# xxxxxx_001_sh1_RTC.net
KiCad netlist of a schematic drawn in Altium Designer
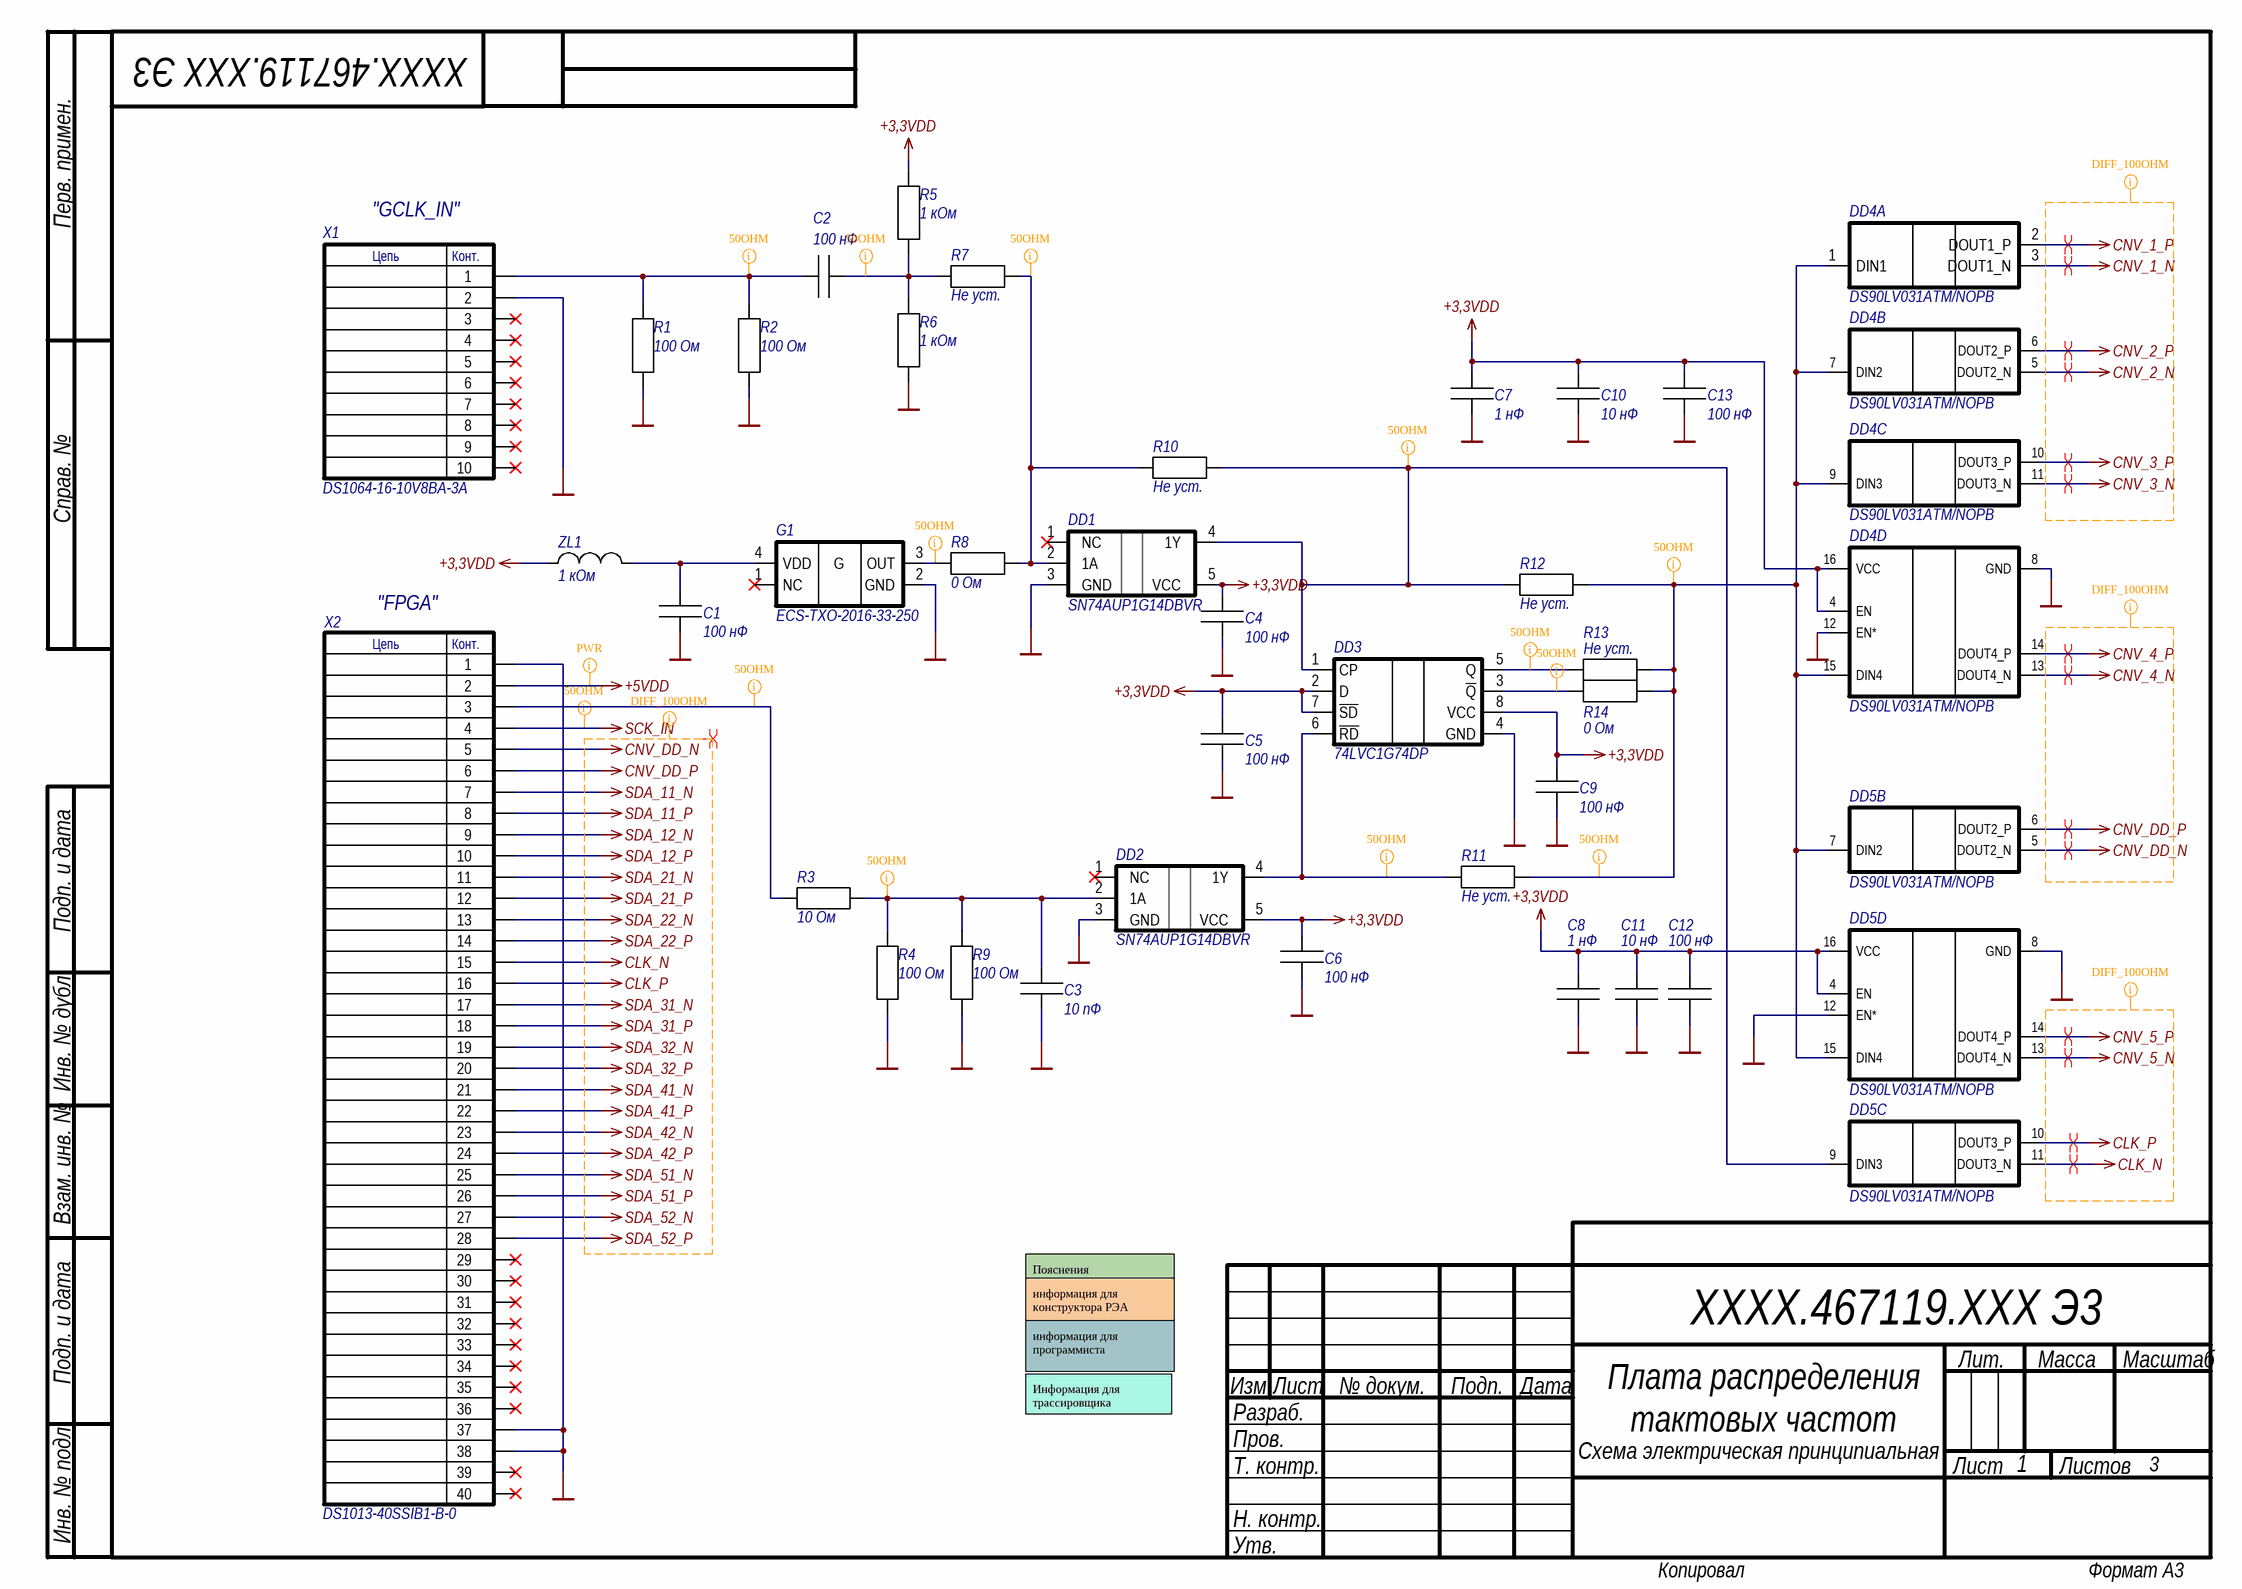
[diagram p0: xxxxxx.001_sh1_RTC.SchDoc]

(export (version "E")
  (design (tool "Eeschema 10.0.6"))
  (components
    (comp (ref "C1")
      (value "100 нФ")
      (footprint "CAPC160X080X080N")
      (description "Chip Monolithic Ceramic Capacitor")
      (fields (field (name "MANUFACTURER") "Murata") (field (name "VOLTAGE") "25 В"))
      (libsource (lib "xxxxxx001_RTC") (part "CAP_NP"))
    )
    (comp (ref "C2")
      (value "100 нФ")
      (footprint "CAPC160X080X080N")
      (description "Chip Monolithic Ceramic Capacitor")
      (fields (field (name "MANUFACTURER") "Murata") (field (name "VOLTAGE") "25 В"))
      (libsource (lib "xxxxxx001_RTC") (part "CAP_NP"))
    )
    (comp (ref "C3")
      (value "10 пФ")
      (footprint "CAPC160X080X080N")
      (description "Multilayer Ceramic Chip Capacitor")
      (fields (field (name "MANUFACTURER") "Yageo") (field (name "VOLTAGE") "50 В"))
      (libsource (lib "xxxxxx001_RTC") (part "CAP_NP"))
    )
    (comp (ref "C4")
      (value "100 нФ")
      (footprint "CAPC160X080X080N")
      (description "Chip Monolithic Ceramic Capacitor")
      (fields (field (name "MANUFACTURER") "Murata") (field (name "VOLTAGE") "25 В"))
      (libsource (lib "xxxxxx001_RTC") (part "CAP_NP"))
    )
    (comp (ref "C5")
      (value "100 нФ")
      (footprint "CAPC160X080X080N")
      (description "Chip Monolithic Ceramic Capacitor")
      (fields (field (name "MANUFACTURER") "Murata") (field (name "VOLTAGE") "25 В"))
      (libsource (lib "xxxxxx001_RTC") (part "CAP_NP"))
    )
    (comp (ref "C6")
      (value "100 нФ")
      (footprint "CAPC160X080X080N")
      (description "Chip Monolithic Ceramic Capacitor")
      (fields (field (name "MANUFACTURER") "Murata") (field (name "VOLTAGE") "25 В"))
      (libsource (lib "xxxxxx001_RTC") (part "CAP_NP"))
    )
    (comp (ref "C7")
      (value "1 нФ")
      (footprint "CAPC160X080X080N")
      (description "Chip Monolithic Ceramic Capacitor")
      (fields (field (name "MANUFACTURER") "Murata") (field (name "VOLTAGE") "50 В"))
      (libsource (lib "xxxxxx001_RTC") (part "CAP_NP"))
    )
    (comp (ref "C8")
      (value "1 нФ")
      (footprint "CAPC160X080X080N")
      (description "Chip Monolithic Ceramic Capacitor")
      (fields (field (name "MANUFACTURER") "Murata") (field (name "VOLTAGE") "50 В"))
      (libsource (lib "xxxxxx001_RTC") (part "CAP_NP"))
    )
    (comp (ref "C9")
      (value "100 нФ")
      (footprint "CAPC160X080X080N")
      (description "Chip Monolithic Ceramic Capacitor")
      (fields (field (name "MANUFACTURER") "Murata") (field (name "VOLTAGE") "25 В"))
      (libsource (lib "xxxxxx001_RTC") (part "CAP_NP"))
    )
    (comp (ref "C10")
      (value "10 нФ")
      (footprint "CAPC160X080X080N")
      (description "Chip Monolithic Ceramic Capacitor")
      (fields (field (name "MANUFACTURER") "Murata") (field (name "VOLTAGE") "25 В"))
      (libsource (lib "xxxxxx001_RTC") (part "CAP_NP"))
    )
    (comp (ref "C11")
      (value "10 нФ")
      (footprint "CAPC160X080X080N")
      (description "Chip Monolithic Ceramic Capacitor")
      (fields (field (name "MANUFACTURER") "Murata") (field (name "VOLTAGE") "25 В"))
      (libsource (lib "xxxxxx001_RTC") (part "CAP_NP"))
    )
    (comp (ref "C12")
      (value "100 нФ")
      (footprint "CAPC160X080X080N")
      (description "Chip Monolithic Ceramic Capacitor")
      (fields (field (name "MANUFACTURER") "Murata") (field (name "VOLTAGE") "25 В"))
      (libsource (lib "xxxxxx001_RTC") (part "CAP_NP"))
    )
    (comp (ref "C13")
      (value "100 нФ")
      (footprint "CAPC160X080X080N")
      (description "Chip Monolithic Ceramic Capacitor")
      (fields (field (name "MANUFACTURER") "Murata") (field (name "VOLTAGE") "25 В"))
      (libsource (lib "xxxxxx001_RTC") (part "CAP_NP"))
    )
    (comp (ref "DD1")
      (value "SN74AUP1G14DBVR")
      (footprint "TI_DBV0005A_SOT23_5")
      (description "Low-Power Single Schmitt-Trigger Inverter")
      (fields (field (name "MANUFACTURER") "Texas Instruments"))
      (libsource (lib "xxxxxx001_RTC") (part "SN74AUP1G14"))
    )
    (comp (ref "DD2")
      (value "SN74AUP1G14DBVR")
      (footprint "TI_DBV0005A_SOT23_5")
      (description "Low-Power Single Schmitt-Trigger Inverter")
      (fields (field (name "MANUFACTURER") "Texas Instruments"))
      (libsource (lib "xxxxxx001_RTC") (part "SN74AUP1G14"))
    )
    (comp (ref "DD3")
      (value "74LVC1G74DP")
      (footprint "TSOP65P400X110-8N")
      (description "Single D-type flip-flop with set and reset")
      (fields (field (name "MANUFACTURER") "Nexperia"))
      (libsource (lib "xxxxxx001_RTC") (part "74LVC1G74"))
    )
    (comp (ref "DD4")
      (value "DS90LV031ATM/NOPB")
      (footprint "SOIC127P600X175-16N")
      (description "3-V LVDS Quad CMOS Differential Line Driver")
      (fields (field (name "MANUFACTURER") "Texas Instruments"))
      (libsource (lib "xxxxxx001_RTC") (part "DS90LV031ATM"))
    )
    (comp (ref "DD5")
      (value "DS90LV031ATM/NOPB")
      (footprint "SOIC127P600X175-16N")
      (description "3-V LVDS Quad CMOS Differential Line Driver")
      (fields (field (name "MANUFACTURER") "Texas Instruments"))
      (libsource (lib "xxxxxx001_RTC") (part "DS90LV031ATM"))
    )
    (comp (ref "G1")
      (value "ECS-TXO-2016-33-250")
      (footprint "OSCCC160X200X80-4N")
      (description "SMD CMOS TCXO, 25 МГц, ±2.5ppm")
      (fields (field (name "MANUFACTURER") "ECS INC INTERNATIONAL"))
      (libsource (lib "xxxxxx001_RTC") (part "GEN"))
    )
    (comp (ref "R1")
      (value "100 Ом")
      (footprint "RESC160X080X045N")
      (description "General Purpose Chip Resistor")
      (fields (field (name "MANUFACTURER") "Yageo") (field (name "POWER") "100 мВт"))
      (libsource (lib "") (part "RES_1"))
    )
    (comp (ref "R2")
      (value "100 Ом")
      (footprint "RESC160X080X045N")
      (description "General Purpose Chip Resistor")
      (fields (field (name "MANUFACTURER") "Yageo") (field (name "POWER") "100 мВт"))
      (libsource (lib "") (part "RES_1"))
    )
    (comp (ref "R3")
      (value "10 Ом")
      (footprint "RESC160X080X045N")
      (description "General Purpose Chip Resistor")
      (fields (field (name "MANUFACTURER") "Yageo") (field (name "POWER") "100 мВт"))
      (libsource (lib "xxxxxx001_RTC") (part "RES"))
    )
    (comp (ref "R4")
      (value "100 Ом")
      (footprint "RESC160X080X045N")
      (description "General Purpose Chip Resistor")
      (fields (field (name "MANUFACTURER") "Yageo") (field (name "POWER") "100 мВт"))
      (libsource (lib "") (part "RES_1"))
    )
    (comp (ref "R5")
      (value "1 кОм")
      (footprint "RESC160X080X045N")
      (description "General Purpose Chip Resistor")
      (fields (field (name "MANUFACTURER") "Yageo") (field (name "POWER") "100 мВт"))
      (libsource (lib "") (part "RES_1"))
    )
    (comp (ref "R6")
      (value "1 кОм")
      (footprint "RESC160X080X045N")
      (description "General Purpose Chip Resistor")
      (fields (field (name "MANUFACTURER") "Yageo") (field (name "POWER") "100 мВт"))
      (libsource (lib "") (part "RES_1"))
    )
    (comp (ref "R7")
      (value "Не уст.")
      (footprint "RESC160X080X045N")
      (description "General Purpose Chip Resistor")
      (fields (field (name "MANUFACTURER") "Yageo") (field (name "POWER") "100 мВт"))
      (libsource (lib "xxxxxx001_RTC") (part "RES"))
    )
    (comp (ref "R8")
      (value "0 Ом")
      (footprint "RESC160X080X045N")
      (description "General Purpose Chip Resistor")
      (fields (field (name "MANUFACTURER") "Yageo") (field (name "POWER") "100 мВт"))
      (libsource (lib "xxxxxx001_RTC") (part "RES"))
    )
    (comp (ref "R9")
      (value "100 Ом")
      (footprint "RESC160X080X045N")
      (description "General Purpose Chip Resistor")
      (fields (field (name "MANUFACTURER") "Yageo") (field (name "POWER") "100 мВт"))
      (libsource (lib "") (part "RES_1"))
    )
    (comp (ref "R10")
      (value "Не уст.")
      (footprint "RESC160X080X045N")
      (description "General Purpose Chip Resistor")
      (fields (field (name "MANUFACTURER") "Yageo") (field (name "POWER") "100 мВт"))
      (libsource (lib "xxxxxx001_RTC") (part "RES"))
    )
    (comp (ref "R11")
      (value "Не уст.")
      (footprint "RESC160X080X045N")
      (description "General Purpose Chip Resistor")
      (fields (field (name "MANUFACTURER") "Yageo") (field (name "POWER") "100 мВт"))
      (libsource (lib "xxxxxx001_RTC") (part "RES"))
    )
    (comp (ref "R12")
      (value "Не уст.")
      (footprint "RESC160X080X045N")
      (description "General Purpose Chip Resistor")
      (fields (field (name "MANUFACTURER") "Yageo") (field (name "POWER") "100 мВт"))
      (libsource (lib "xxxxxx001_RTC") (part "RES"))
    )
    (comp (ref "R13")
      (value "Не уст.")
      (footprint "RESC160X080X045N")
      (description "General Purpose Chip Resistor")
      (fields (field (name "MANUFACTURER") "Yageo") (field (name "POWER") "100 мВт"))
      (libsource (lib "xxxxxx001_RTC") (part "RES"))
    )
    (comp (ref "R14")
      (value "0 Ом")
      (footprint "RESC160X080X045N")
      (description "General Purpose Chip Resistor")
      (fields (field (name "MANUFACTURER") "Yageo") (field (name "POWER") "100 мВт"))
      (libsource (lib "xxxxxx001_RTC") (part "RES"))
    )
    (comp (ref "X1")
      (value "DS1064-16-10V8BA-3A")
      (footprint "BHTH127x254_2X5")
      (description "1.27mm Box Header V/T Type H=7.1mm, 10 pin")
      (fields (field (name "MANUFACTURER") "Connfly"))
      (libsource (lib "xxxxxx001_RTC") (part "CONN_10P"))
    )
    (comp (ref "X2")
      (value "DS1013-40SSIB1-B-0")
      (footprint "BHTH254_2X20")
      (description "2.54mm Box Header, Two Rows, 40 pins")
      (fields (field (name "MANUFACTURER") "Connfly"))
      (libsource (lib "xxxxxx001_RTC") (part "CONN_40P"))
    )
    (comp (ref "ZL1")
      (value "1 кОм")
      (footprint "INDC100X050X050N")
      (description "Chip Ferrite Bead")
      (fields (field (name "MANUFACTURER") "Murata") (field (name "TOLERANCE") "±25%"))
      (libsource (lib "xxxxxx001_RTC") (part "IND_NP"))
    )
  )
  (nets
    (net (code "1") (name "+3,3VDD") (class "Default")
      (node (ref "C10") (pin "1") (pinfunction "1_1") (pintype "passive"))
      (node (ref "C11") (pin "1") (pinfunction "1_1") (pintype "passive"))
      (node (ref "C12") (pin "1") (pinfunction "1_1") (pintype "passive"))
      (node (ref "C13") (pin "1") (pinfunction "1_1") (pintype "passive"))
      (node (ref "C4") (pin "1") (pinfunction "1_1") (pintype "passive"))
      (node (ref "C5") (pin "1") (pinfunction "1_1") (pintype "passive"))
      (node (ref "C6") (pin "1") (pinfunction "1_1") (pintype "passive"))
      (node (ref "C7") (pin "1") (pinfunction "1_1") (pintype "passive"))
      (node (ref "C8") (pin "1") (pinfunction "1_1") (pintype "passive"))
      (node (ref "C9") (pin "1") (pinfunction "1_1") (pintype "passive"))
      (node (ref "DD1") (pin "5") (pinfunction "VCC_5") (pintype "passive"))
      (node (ref "DD2") (pin "5") (pinfunction "VCC_5") (pintype "passive"))
      (node (ref "DD3") (pin "2") (pinfunction "D_2") (pintype "passive"))
      (node (ref "DD3") (pin "7") (pinfunction "SD_7") (pintype "passive"))
      (node (ref "DD3") (pin "8") (pinfunction "VCC_8") (pintype "passive"))
      (node (ref "DD4") (pin "16") (pinfunction "VCC_16") (pintype "passive"))
      (node (ref "DD4") (pin "4") (pinfunction "EN_4") (pintype "passive"))
      (node (ref "DD5") (pin "16") (pinfunction "VCC_16") (pintype "passive"))
      (node (ref "DD5") (pin "4") (pinfunction "EN_4") (pintype "passive"))
      (node (ref "R5") (pin "1") (pinfunction "1_1") (pintype "passive"))
      (node (ref "ZL1") (pin "1") (pinfunction "1_1") (pintype "passive"))
    )
    (net (code "2") (name "+5VDD") (class "Default")
      (node (ref "X2") (pin "2") (pinfunction "2_2") (pintype "passive"))
    )
    (net (code "3") (name "CLK_N") (class "Default")
      (node (ref "DD5") (pin "11") (pinfunction "DOUT3_N_11") (pintype "passive"))
      (node (ref "X2") (pin "15") (pinfunction "15_15") (pintype "passive"))
    )
    (net (code "4") (name "CLK_P") (class "Default")
      (node (ref "DD5") (pin "10") (pinfunction "DOUT3_P_10") (pintype "passive"))
      (node (ref "X2") (pin "16") (pinfunction "16_16") (pintype "passive"))
    )
    (net (code "5") (name "CNV_1_N") (class "Default")
      (node (ref "DD4") (pin "3") (pinfunction "DOUT1_N_3") (pintype "passive"))
    )
    (net (code "6") (name "CNV_1_P") (class "Default")
      (node (ref "DD4") (pin "2") (pinfunction "DOUT1_P_2") (pintype "passive"))
    )
    (net (code "7") (name "CNV_2_N") (class "Default")
      (node (ref "DD4") (pin "5") (pinfunction "DOUT2_N_5") (pintype "passive"))
    )
    (net (code "8") (name "CNV_2_P") (class "Default")
      (node (ref "DD4") (pin "6") (pinfunction "DOUT2_P_6") (pintype "passive"))
    )
    (net (code "9") (name "CNV_3_N") (class "Default")
      (node (ref "DD4") (pin "11") (pinfunction "DOUT3_N_11") (pintype "passive"))
    )
    (net (code "10") (name "CNV_3_P") (class "Default")
      (node (ref "DD4") (pin "10") (pinfunction "DOUT3_P_10") (pintype "passive"))
    )
    (net (code "11") (name "CNV_4_N") (class "Default")
      (node (ref "DD4") (pin "13") (pinfunction "DOUT4_N_13") (pintype "passive"))
    )
    (net (code "12") (name "CNV_4_P") (class "Default")
      (node (ref "DD4") (pin "14") (pinfunction "DOUT4_P_14") (pintype "passive"))
    )
    (net (code "13") (name "CNV_5_N") (class "Default")
      (node (ref "DD5") (pin "13") (pinfunction "DOUT4_N_13") (pintype "passive"))
    )
    (net (code "14") (name "CNV_5_P") (class "Default")
      (node (ref "DD5") (pin "14") (pinfunction "DOUT4_P_14") (pintype "passive"))
    )
    (net (code "15") (name "CNV_DD_N") (class "Default")
      (node (ref "DD5") (pin "5") (pinfunction "DOUT2_N_5") (pintype "passive"))
      (node (ref "X2") (pin "5") (pinfunction "5_5") (pintype "passive"))
    )
    (net (code "16") (name "CNV_DD_P") (class "Default")
      (node (ref "DD5") (pin "6") (pinfunction "DOUT2_P_6") (pintype "passive"))
      (node (ref "X2") (pin "6") (pinfunction "6_6") (pintype "passive"))
    )
    (net (code "17") (name "GND") (class "Default")
      (node (ref "C1") (pin "2") (pinfunction "2_2") (pintype "passive"))
      (node (ref "C10") (pin "2") (pinfunction "2_2") (pintype "passive"))
      (node (ref "C11") (pin "2") (pinfunction "2_2") (pintype "passive"))
      (node (ref "C12") (pin "2") (pinfunction "2_2") (pintype "passive"))
      (node (ref "C13") (pin "2") (pinfunction "2_2") (pintype "passive"))
      (node (ref "C3") (pin "2") (pinfunction "2_2") (pintype "passive"))
      (node (ref "C4") (pin "2") (pinfunction "2_2") (pintype "passive"))
      (node (ref "C5") (pin "2") (pinfunction "2_2") (pintype "passive"))
      (node (ref "C6") (pin "2") (pinfunction "2_2") (pintype "passive"))
      (node (ref "C7") (pin "2") (pinfunction "2_2") (pintype "passive"))
      (node (ref "C8") (pin "2") (pinfunction "2_2") (pintype "passive"))
      (node (ref "C9") (pin "2") (pinfunction "2_2") (pintype "passive"))
      (node (ref "DD1") (pin "3") (pinfunction "GND_3") (pintype "passive"))
      (node (ref "DD2") (pin "3") (pinfunction "GND_3") (pintype "passive"))
      (node (ref "DD3") (pin "4") (pinfunction "GND_4") (pintype "passive"))
      (node (ref "DD4") (pin "12") (pinfunction "EN*_12") (pintype "passive"))
      (node (ref "DD4") (pin "8") (pinfunction "GND_8") (pintype "passive"))
      (node (ref "DD5") (pin "12") (pinfunction "EN*_12") (pintype "passive"))
      (node (ref "DD5") (pin "8") (pinfunction "GND_8") (pintype "passive"))
      (node (ref "G1") (pin "2") (pinfunction "GND_2") (pintype "passive"))
      (node (ref "R1") (pin "2") (pinfunction "2_2") (pintype "passive"))
      (node (ref "R2") (pin "2") (pinfunction "2_2") (pintype "passive"))
      (node (ref "R4") (pin "2") (pinfunction "2_2") (pintype "passive"))
      (node (ref "R6") (pin "2") (pinfunction "2_2") (pintype "passive"))
      (node (ref "R9") (pin "2") (pinfunction "2_2") (pintype "passive"))
      (node (ref "X1") (pin "2") (pinfunction "2_2") (pintype "passive"))
      (node (ref "X2") (pin "1") (pinfunction "1_1") (pintype "passive"))
      (node (ref "X2") (pin "37") (pinfunction "37_37") (pintype "passive"))
      (node (ref "X2") (pin "38") (pinfunction "38_38") (pintype "passive"))
    )
    (net (code "18") (name "Net-(C2-Pad1)") (class "Default")
      (node (ref "C2") (pin "1") (pinfunction "1_1") (pintype "passive"))
      (node (ref "R1") (pin "1") (pinfunction "1_1") (pintype "passive"))
      (node (ref "R2") (pin "1") (pinfunction "1_1") (pintype "passive"))
      (node (ref "X1") (pin "1") (pinfunction "1_1") (pintype "passive"))
    )
    (net (code "19") (name "Net-(C2-Pad2)") (class "Default")
      (node (ref "C2") (pin "2") (pinfunction "2_2") (pintype "passive"))
      (node (ref "R5") (pin "2") (pinfunction "2_2") (pintype "passive"))
      (node (ref "R6") (pin "1") (pinfunction "1_1") (pintype "passive"))
      (node (ref "R7") (pin "1") (pinfunction "1_1") (pintype "passive"))
    )
    (net (code "20") (name "Net-(DD1-1A)") (class "Default")
      (node (ref "DD1") (pin "2") (pinfunction "1A_2") (pintype "passive"))
      (node (ref "R10") (pin "1") (pinfunction "1_1") (pintype "passive"))
      (node (ref "R7") (pin "2") (pinfunction "2_2") (pintype "passive"))
      (node (ref "R8") (pin "2") (pinfunction "2_2") (pintype "passive"))
    )
    (net (code "21") (name "Net-(DD1-1Y)") (class "Default")
      (node (ref "DD1") (pin "4") (pinfunction "1Y_4") (pintype "passive"))
      (node (ref "DD3") (pin "1") (pinfunction "CP_1") (pintype "passive"))
      (node (ref "DD5") (pin "9") (pinfunction "DIN3_9") (pintype "passive"))
      (node (ref "R10") (pin "2") (pinfunction "2_2") (pintype "passive"))
      (node (ref "R12") (pin "1") (pinfunction "1_1") (pintype "passive"))
    )
    (net (code "22") (name "Net-(DD2-1A)") (class "Default")
      (node (ref "C3") (pin "1") (pinfunction "1_1") (pintype "passive"))
      (node (ref "DD2") (pin "2") (pinfunction "1A_2") (pintype "passive"))
      (node (ref "R3") (pin "2") (pinfunction "2_2") (pintype "passive"))
      (node (ref "R4") (pin "1") (pinfunction "1_1") (pintype "passive"))
      (node (ref "R9") (pin "1") (pinfunction "1_1") (pintype "passive"))
    )
    (net (code "23") (name "Net-(DD2-1Y)") (class "Default")
      (node (ref "DD2") (pin "4") (pinfunction "1Y_4") (pintype "passive"))
      (node (ref "DD3") (pin "6") (pinfunction "RD_6") (pintype "passive"))
      (node (ref "R11") (pin "1") (pinfunction "1_1") (pintype "passive"))
    )
    (net (code "24") (name "Net-(DD3-Q-Pad3)") (class "Default")
      (node (ref "DD3") (pin "3") (pinfunction "Q_3") (pintype "passive"))
      (node (ref "R14") (pin "1") (pinfunction "1_1") (pintype "passive"))
    )
    (net (code "25") (name "Net-(DD3-Q-Pad5)") (class "Default")
      (node (ref "DD3") (pin "5") (pinfunction "Q_5") (pintype "passive"))
      (node (ref "R13") (pin "1") (pinfunction "1_1") (pintype "passive"))
    )
    (net (code "26") (name "Net-(DD4A-DIN1)") (class "Default")
      (node (ref "DD4") (pin "1") (pinfunction "DIN1_1") (pintype "passive"))
      (node (ref "DD4") (pin "15") (pinfunction "DIN4_15") (pintype "passive"))
      (node (ref "DD4") (pin "7") (pinfunction "DIN2_7") (pintype "passive"))
      (node (ref "DD4") (pin "9") (pinfunction "DIN3_9") (pintype "passive"))
      (node (ref "DD5") (pin "15") (pinfunction "DIN4_15") (pintype "passive"))
      (node (ref "DD5") (pin "7") (pinfunction "DIN2_7") (pintype "passive"))
      (node (ref "R11") (pin "2") (pinfunction "2_2") (pintype "passive"))
      (node (ref "R12") (pin "2") (pinfunction "2_2") (pintype "passive"))
      (node (ref "R13") (pin "2") (pinfunction "2_2") (pintype "passive"))
      (node (ref "R14") (pin "2") (pinfunction "2_2") (pintype "passive"))
    )
    (net (code "27") (name "Net-(G1-OUT)") (class "Default")
      (node (ref "G1") (pin "3") (pinfunction "OUT_3") (pintype "passive"))
      (node (ref "R8") (pin "1") (pinfunction "1_1") (pintype "passive"))
    )
    (net (code "28") (name "Net-(G1-VDD)") (class "Default")
      (node (ref "C1") (pin "1") (pinfunction "1_1") (pintype "passive"))
      (node (ref "G1") (pin "4") (pinfunction "VDD_4") (pintype "passive"))
      (node (ref "ZL1") (pin "2") (pinfunction "2_2") (pintype "passive"))
    )
    (net (code "29") (name "Net-(R3-Pad1)") (class "Default")
      (node (ref "R3") (pin "1") (pinfunction "1_1") (pintype "passive"))
      (node (ref "X2") (pin "3") (pinfunction "3_3") (pintype "passive"))
    )
    (net (code "30") (name "SCK_IN") (class "Default")
      (node (ref "X2") (pin "4") (pinfunction "4_4") (pintype "passive"))
    )
    (net (code "31") (name "SDA_11_N") (class "Default")
      (node (ref "X2") (pin "7") (pinfunction "7_7") (pintype "passive"))
    )
    (net (code "32") (name "SDA_11_P") (class "Default")
      (node (ref "X2") (pin "8") (pinfunction "8_8") (pintype "passive"))
    )
    (net (code "33") (name "SDA_12_N") (class "Default")
      (node (ref "X2") (pin "9") (pinfunction "9_9") (pintype "passive"))
    )
    (net (code "34") (name "SDA_12_P") (class "Default")
      (node (ref "X2") (pin "10") (pinfunction "10_10") (pintype "passive"))
    )
    (net (code "35") (name "SDA_21_N") (class "Default")
      (node (ref "X2") (pin "11") (pinfunction "11_11") (pintype "passive"))
    )
    (net (code "36") (name "SDA_21_P") (class "Default")
      (node (ref "X2") (pin "12") (pinfunction "12_12") (pintype "passive"))
    )
    (net (code "37") (name "SDA_22_N") (class "Default")
      (node (ref "X2") (pin "13") (pinfunction "13_13") (pintype "passive"))
    )
    (net (code "38") (name "SDA_22_P") (class "Default")
      (node (ref "X2") (pin "14") (pinfunction "14_14") (pintype "passive"))
    )
    (net (code "39") (name "SDA_31_N") (class "Default")
      (node (ref "X2") (pin "17") (pinfunction "17_17") (pintype "passive"))
    )
    (net (code "40") (name "SDA_31_P") (class "Default")
      (node (ref "X2") (pin "18") (pinfunction "18_18") (pintype "passive"))
    )
    (net (code "41") (name "SDA_32_N") (class "Default")
      (node (ref "X2") (pin "19") (pinfunction "19_19") (pintype "passive"))
    )
    (net (code "42") (name "SDA_32_P") (class "Default")
      (node (ref "X2") (pin "20") (pinfunction "20_20") (pintype "passive"))
    )
    (net (code "43") (name "SDA_41_N") (class "Default")
      (node (ref "X2") (pin "21") (pinfunction "21_21") (pintype "passive"))
    )
    (net (code "44") (name "SDA_41_P") (class "Default")
      (node (ref "X2") (pin "22") (pinfunction "22_22") (pintype "passive"))
    )
    (net (code "45") (name "SDA_42_N") (class "Default")
      (node (ref "X2") (pin "23") (pinfunction "23_23") (pintype "passive"))
    )
    (net (code "46") (name "SDA_42_P") (class "Default")
      (node (ref "X2") (pin "24") (pinfunction "24_24") (pintype "passive"))
    )
    (net (code "47") (name "SDA_51_N") (class "Default")
      (node (ref "X2") (pin "25") (pinfunction "25_25") (pintype "passive"))
    )
    (net (code "48") (name "SDA_51_P") (class "Default")
      (node (ref "X2") (pin "26") (pinfunction "26_26") (pintype "passive"))
    )
    (net (code "49") (name "SDA_52_N") (class "Default")
      (node (ref "X2") (pin "27") (pinfunction "27_27") (pintype "passive"))
    )
    (net (code "50") (name "SDA_52_P") (class "Default")
      (node (ref "X2") (pin "28") (pinfunction "28_28") (pintype "passive"))
    )
    (net (code "51") (name "unconnected-(DD1-NC-Pad1)") (class "Default")
      (node (ref "DD1") (pin "1") (pinfunction "NC_1") (pintype "passive+no_connect"))
    )
    (net (code "52") (name "unconnected-(DD2-NC-Pad1)") (class "Default")
      (node (ref "DD2") (pin "1") (pinfunction "NC_1") (pintype "passive+no_connect"))
    )
    (net (code "53") (name "unconnected-(G1-NC-Pad1)") (class "Default")
      (node (ref "G1") (pin "1") (pinfunction "NC_1") (pintype "passive+no_connect"))
    )
    (net (code "54") (name "unconnected-(X1-Pad3)") (class "Default")
      (node (ref "X1") (pin "3") (pinfunction "3_3") (pintype "passive+no_connect"))
    )
    (net (code "55") (name "unconnected-(X1-Pad4)") (class "Default")
      (node (ref "X1") (pin "4") (pinfunction "4_4") (pintype "passive+no_connect"))
    )
    (net (code "56") (name "unconnected-(X1-Pad5)") (class "Default")
      (node (ref "X1") (pin "5") (pinfunction "5_5") (pintype "passive+no_connect"))
    )
    (net (code "57") (name "unconnected-(X1-Pad6)") (class "Default")
      (node (ref "X1") (pin "6") (pinfunction "6_6") (pintype "passive+no_connect"))
    )
    (net (code "58") (name "unconnected-(X1-Pad7)") (class "Default")
      (node (ref "X1") (pin "7") (pinfunction "7_7") (pintype "passive+no_connect"))
    )
    (net (code "59") (name "unconnected-(X1-Pad8)") (class "Default")
      (node (ref "X1") (pin "8") (pinfunction "8_8") (pintype "passive+no_connect"))
    )
    (net (code "60") (name "unconnected-(X1-Pad9)") (class "Default")
      (node (ref "X1") (pin "9") (pinfunction "9_9") (pintype "passive+no_connect"))
    )
    (net (code "61") (name "unconnected-(X1-Pad10)") (class "Default")
      (node (ref "X1") (pin "10") (pinfunction "10_10") (pintype "passive+no_connect"))
    )
    (net (code "62") (name "unconnected-(X2-Pad29)") (class "Default")
      (node (ref "X2") (pin "29") (pinfunction "29_29") (pintype "passive+no_connect"))
    )
    (net (code "63") (name "unconnected-(X2-Pad30)") (class "Default")
      (node (ref "X2") (pin "30") (pinfunction "30_30") (pintype "passive+no_connect"))
    )
    (net (code "64") (name "unconnected-(X2-Pad31)") (class "Default")
      (node (ref "X2") (pin "31") (pinfunction "31_31") (pintype "passive+no_connect"))
    )
    (net (code "65") (name "unconnected-(X2-Pad32)") (class "Default")
      (node (ref "X2") (pin "32") (pinfunction "32_32") (pintype "passive+no_connect"))
    )
    (net (code "66") (name "unconnected-(X2-Pad33)") (class "Default")
      (node (ref "X2") (pin "33") (pinfunction "33_33") (pintype "passive+no_connect"))
    )
    (net (code "67") (name "unconnected-(X2-Pad34)") (class "Default")
      (node (ref "X2") (pin "34") (pinfunction "34_34") (pintype "passive+no_connect"))
    )
    (net (code "68") (name "unconnected-(X2-Pad35)") (class "Default")
      (node (ref "X2") (pin "35") (pinfunction "35_35") (pintype "passive+no_connect"))
    )
    (net (code "69") (name "unconnected-(X2-Pad36)") (class "Default")
      (node (ref "X2") (pin "36") (pinfunction "36_36") (pintype "passive+no_connect"))
    )
    (net (code "70") (name "unconnected-(X2-Pad39)") (class "Default")
      (node (ref "X2") (pin "39") (pinfunction "39_39") (pintype "passive+no_connect"))
    )
    (net (code "71") (name "unconnected-(X2-Pad40)") (class "Default")
      (node (ref "X2") (pin "40") (pinfunction "40_40") (pintype "passive+no_connect"))
    )
  )
)
